# Bit_Reactor_modular.net
KiCad netlist of a schematic drawn in EAGLE
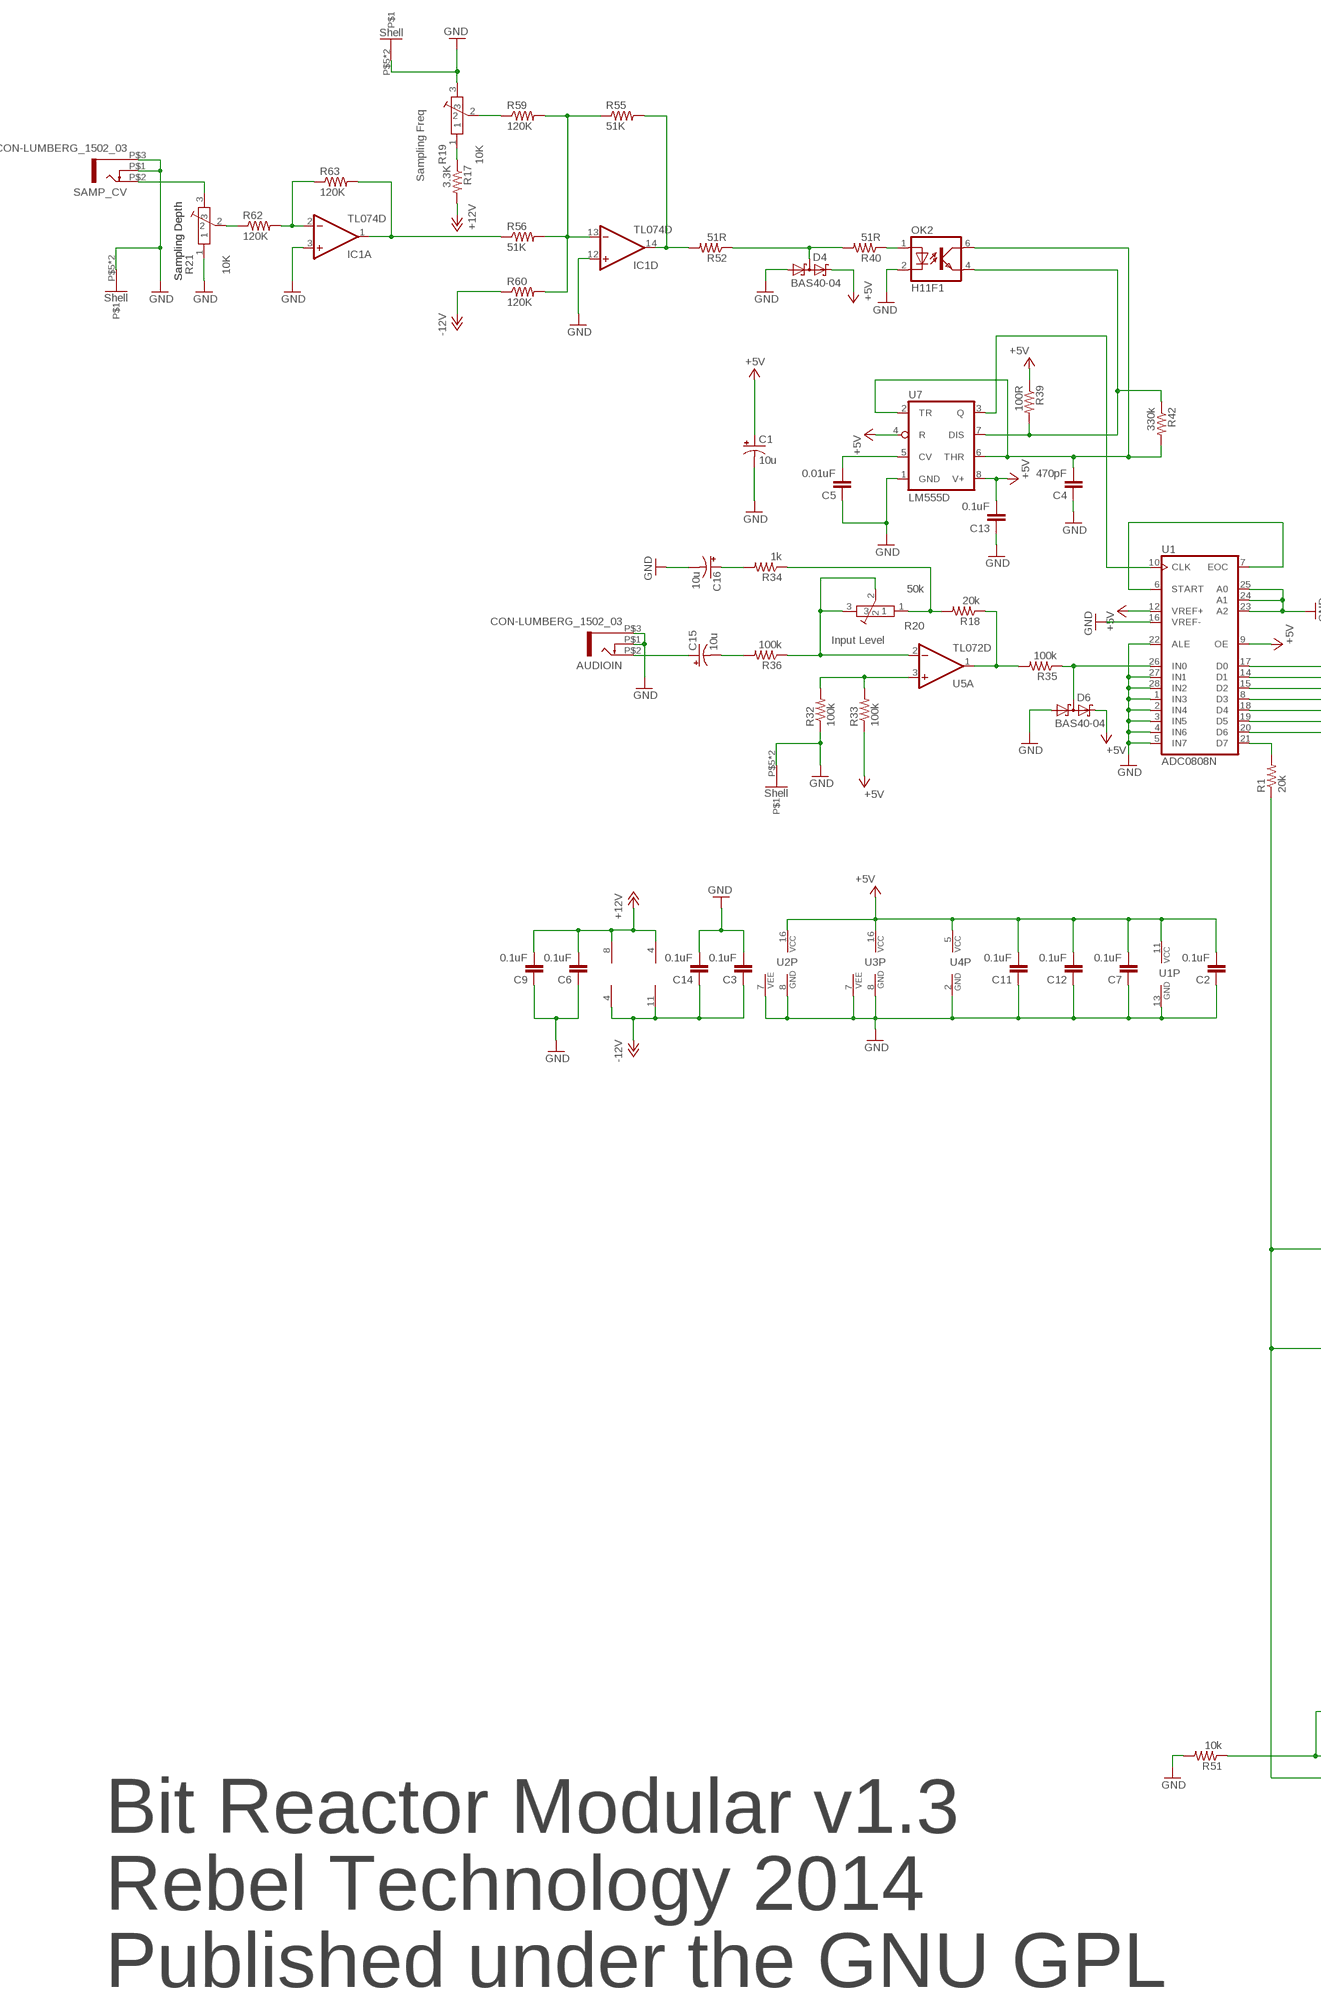
[diagram p0: schematic, sheet 1, part 1 of 2]
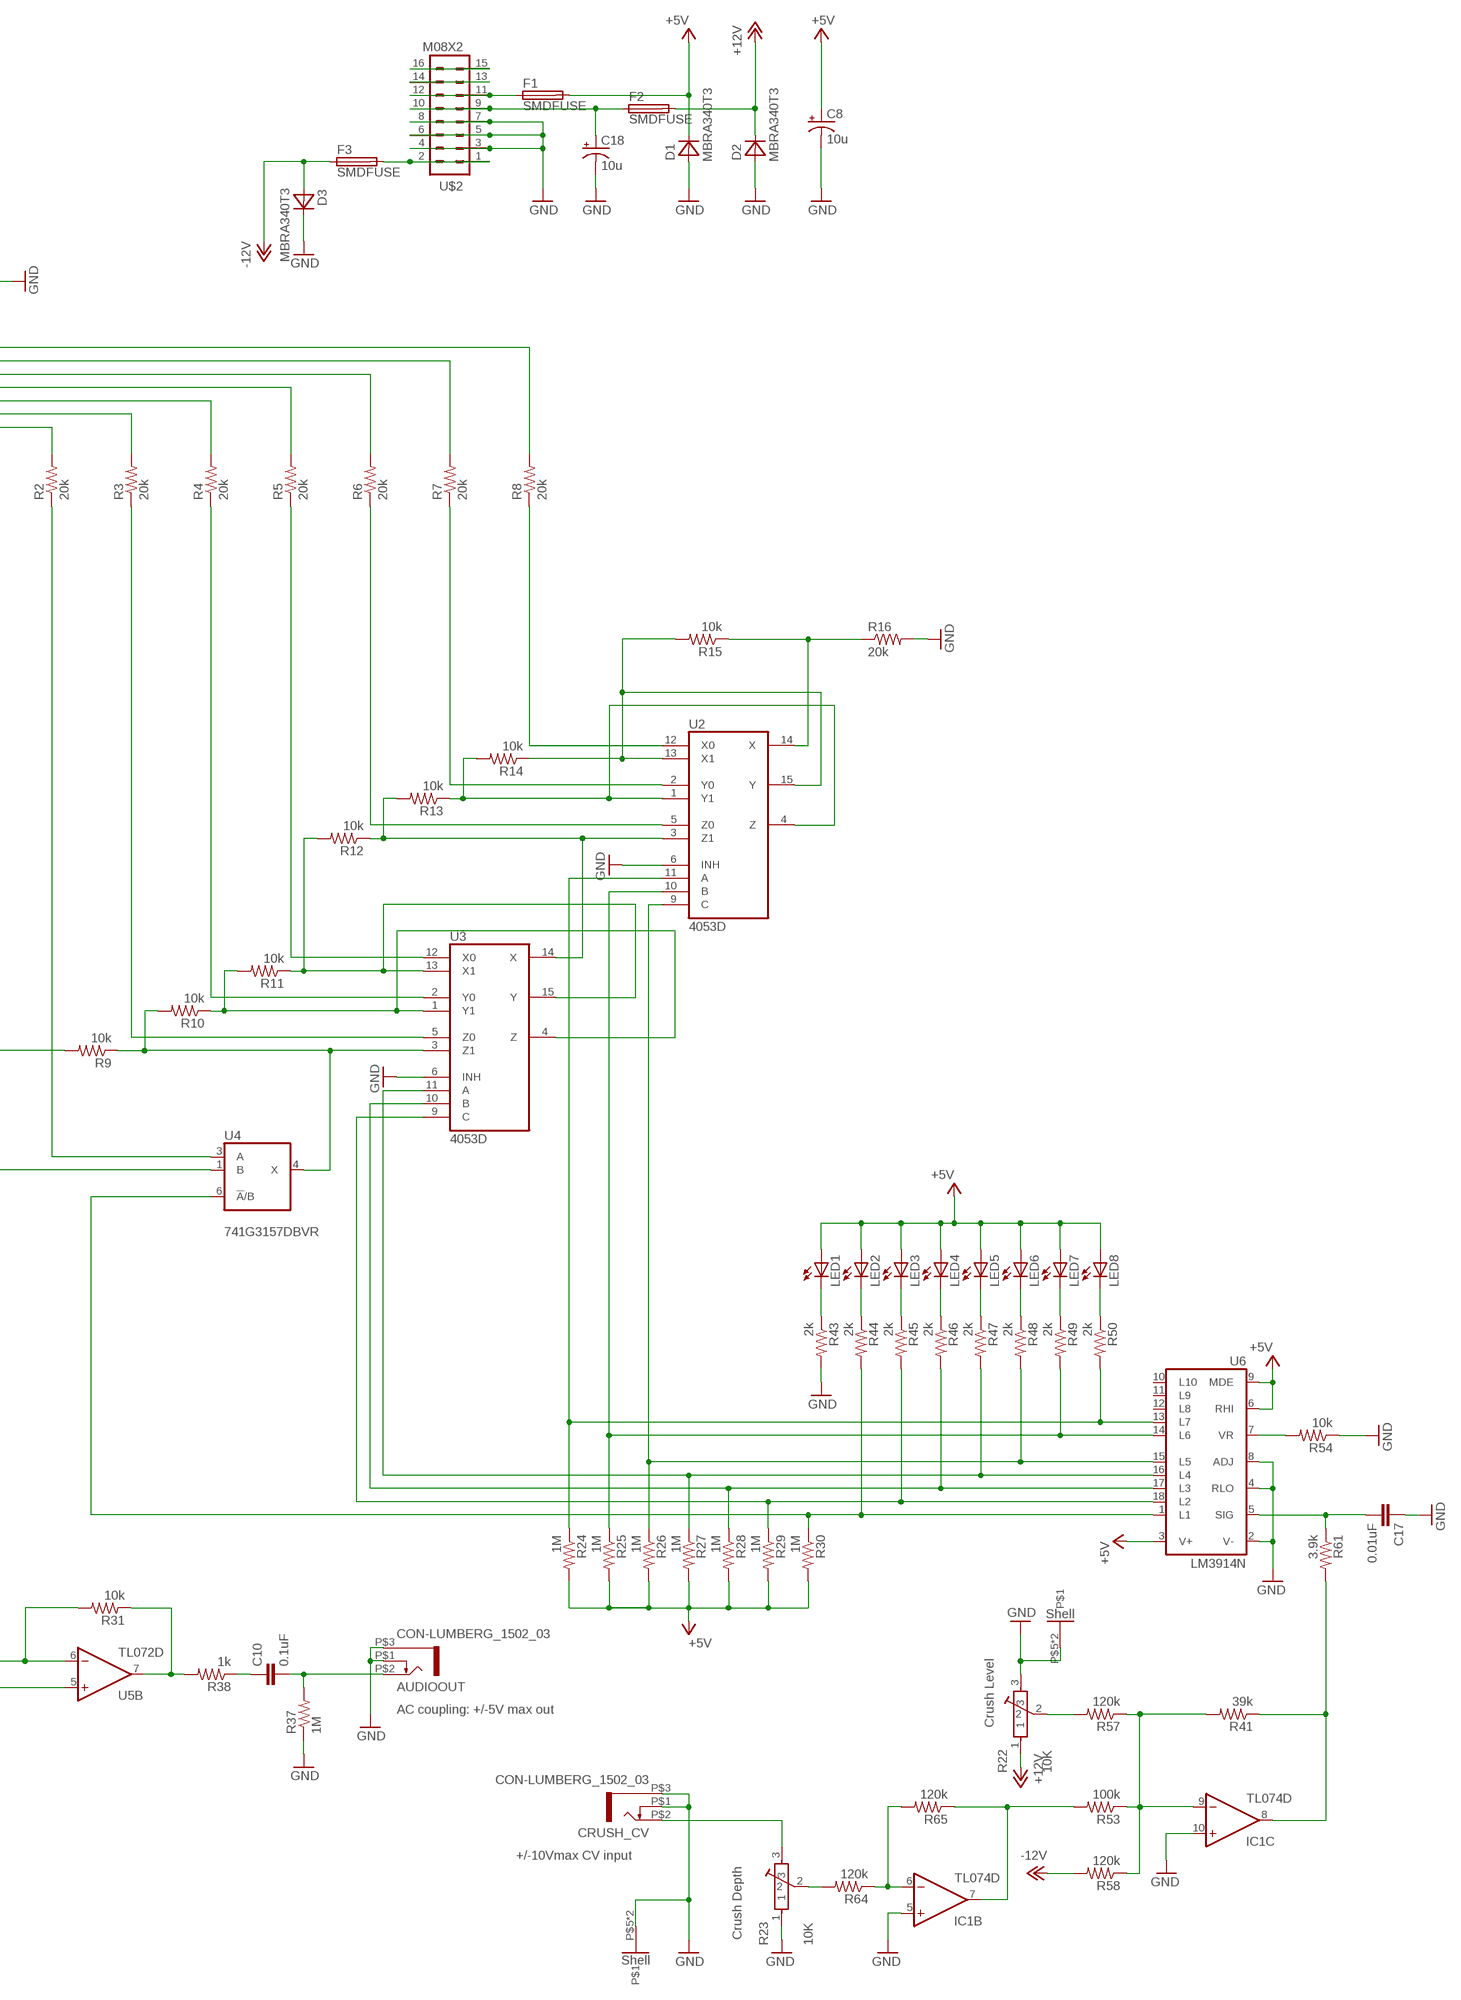
[diagram p1: schematic, sheet 1, part 2 of 2]

(export (version "E")
  (design (tool "Eeschema 10.0.6"))
  (components
    (comp (ref "AUDIOIN")
      (value "CON-LUMBERG_1502_03")
      (footprint "eagle-import:CON-LUMBERG_1502_03")
      (libsource (lib "eagle-import") (part "CON-LUMBERG_1502_03"))
    )
    (comp (ref "AUDIOOUT")
      (value "CON-LUMBERG_1502_03")
      (footprint "eagle-import:CON-LUMBERG_1502_03")
      (libsource (lib "eagle-import") (part "CON-LUMBERG_1502_03"))
    )
    (comp (ref "C1")
      (value "10u")
      (footprint "eagle-import:E2-5")
      (libsource (lib "eagle-import") (part "CPOL-USE2-5"))
    )
    (comp (ref "C2")
      (value "0.1uF")
      (footprint "eagle-import:C0402")
      (libsource (lib "eagle-import") (part "C-EUC0402"))
    )
    (comp (ref "C3")
      (value "0.1uF")
      (footprint "eagle-import:C0402")
      (libsource (lib "eagle-import") (part "C-EUC0402"))
    )
    (comp (ref "C4")
      (value "470pF")
      (footprint "eagle-import:C0402")
      (libsource (lib "eagle-import") (part "C-EUC0402"))
    )
    (comp (ref "C5")
      (value "0.01uF")
      (footprint "eagle-import:C0402")
      (libsource (lib "eagle-import") (part "C-EUC0402"))
    )
    (comp (ref "C6")
      (value "0.1uF")
      (footprint "eagle-import:C0402")
      (libsource (lib "eagle-import") (part "C-EUC0402"))
    )
    (comp (ref "C7")
      (value "0.1uF")
      (footprint "eagle-import:C0402")
      (libsource (lib "eagle-import") (part "C-EUC0402"))
    )
    (comp (ref "C8")
      (value "10u")
      (footprint "eagle-import:E2-5")
      (libsource (lib "eagle-import") (part "CPOL-USE2-5"))
    )
    (comp (ref "C9")
      (value "0.1uF")
      (footprint "eagle-import:C0402")
      (libsource (lib "eagle-import") (part "C-EUC0402"))
    )
    (comp (ref "C10")
      (value "0.1uF")
      (footprint "eagle-import:C0402")
      (libsource (lib "eagle-import") (part "C-EUC0402"))
    )
    (comp (ref "C11")
      (value "0.1uF")
      (footprint "eagle-import:C0402")
      (libsource (lib "eagle-import") (part "C-EUC0402"))
    )
    (comp (ref "C12")
      (value "0.1uF")
      (footprint "eagle-import:C0402")
      (libsource (lib "eagle-import") (part "C-EUC0402"))
    )
    (comp (ref "C13")
      (value "0.1uF")
      (footprint "eagle-import:C0402")
      (libsource (lib "eagle-import") (part "C-EUC0402"))
    )
    (comp (ref "C14")
      (value "0.1uF")
      (footprint "eagle-import:C0402")
      (libsource (lib "eagle-import") (part "C-EUC0402"))
    )
    (comp (ref "C15")
      (value "10u")
      (footprint "eagle-import:E2-5")
      (libsource (lib "eagle-import") (part "CPOL-USE2-5"))
    )
    (comp (ref "C16")
      (value "10u")
      (footprint "eagle-import:E2-5")
      (libsource (lib "eagle-import") (part "CPOL-USE2-5"))
    )
    (comp (ref "C17")
      (value "0.01uF")
      (footprint "eagle-import:C0402")
      (libsource (lib "eagle-import") (part "C-EUC0402"))
    )
    (comp (ref "C18")
      (value "10u")
      (footprint "eagle-import:E2-5")
      (libsource (lib "eagle-import") (part "CPOL-USE2-5"))
    )
    (comp (ref "CRUSH_CV")
      (value "CON-LUMBERG_1502_03")
      (footprint "eagle-import:CON-LUMBERG_1502_03")
      (libsource (lib "eagle-import") (part "CON-LUMBERG_1502_03"))
    )
    (comp (ref "D1")
      (value "MBRA340T3")
      (footprint "eagle-import:SMA")
      (libsource (lib "eagle-import") (part "MBRA340T3"))
    )
    (comp (ref "D2")
      (value "MBRA340T3")
      (footprint "eagle-import:SMA")
      (libsource (lib "eagle-import") (part "MBRA340T3"))
    )
    (comp (ref "D3")
      (value "MBRA340T3")
      (footprint "eagle-import:SMA")
      (libsource (lib "eagle-import") (part "MBRA340T3"))
    )
    (comp (ref "D4")
      (value "BAS40-04")
      (footprint "eagle-import:SOT23")
      (libsource (lib "eagle-import") (part "BAS40-04"))
    )
    (comp (ref "D6")
      (value "BAS40-04")
      (footprint "eagle-import:SOT23")
      (libsource (lib "eagle-import") (part "BAS40-04"))
    )
    (comp (ref "F1")
      (value "SMDFUSE")
      (footprint "eagle-import:1206")
      (libsource (lib "eagle-import") (part "SMDFUSE"))
    )
    (comp (ref "F2")
      (value "SMDFUSE")
      (footprint "eagle-import:1206")
      (libsource (lib "eagle-import") (part "SMDFUSE"))
    )
    (comp (ref "F3")
      (value "SMDFUSE")
      (footprint "eagle-import:1206")
      (libsource (lib "eagle-import") (part "SMDFUSE"))
    )
    (comp (ref "IC1")
      (value "TL074D")
      (footprint "eagle-import:SO14")
      (libsource (lib "eagle-import") (part "TL074D"))
    )
    (comp (ref "LED1")
      (value "LED3MM")
      (footprint "eagle-import:LED3MM")
      (libsource (lib "eagle-import") (part "LED3MM"))
    )
    (comp (ref "LED2")
      (value "LED3MM")
      (footprint "eagle-import:LED3MM")
      (libsource (lib "eagle-import") (part "LED3MM"))
    )
    (comp (ref "LED3")
      (value "LED3MM")
      (footprint "eagle-import:LED3MM")
      (libsource (lib "eagle-import") (part "LED3MM"))
    )
    (comp (ref "LED4")
      (value "LED3MM")
      (footprint "eagle-import:LED3MM")
      (libsource (lib "eagle-import") (part "LED3MM"))
    )
    (comp (ref "LED5")
      (value "LED3MM")
      (footprint "eagle-import:LED3MM")
      (libsource (lib "eagle-import") (part "LED3MM"))
    )
    (comp (ref "LED6")
      (value "LED3MM")
      (footprint "eagle-import:LED3MM")
      (libsource (lib "eagle-import") (part "LED3MM"))
    )
    (comp (ref "LED7")
      (value "LED3MM")
      (footprint "eagle-import:LED3MM")
      (libsource (lib "eagle-import") (part "LED3MM"))
    )
    (comp (ref "LED8")
      (value "LED3MM")
      (footprint "eagle-import:LED3MM")
      (libsource (lib "eagle-import") (part "LED3MM"))
    )
    (comp (ref "OK2")
      (value "H11F1")
      (footprint "eagle-import:DIL05")
      (fields (field (name "OC_FARNELL") "unknown") (field (name "OC_NEWARK") "unknown"))
      (libsource (lib "eagle-import") (part "H11F1"))
    )
    (comp (ref "R1")
      (value "20k")
      (footprint "eagle-import:R0805")
      (libsource (lib "eagle-import") (part "R-US_R0805"))
    )
    (comp (ref "R2")
      (value "20k")
      (footprint "eagle-import:R0805")
      (libsource (lib "eagle-import") (part "R-US_R0805"))
    )
    (comp (ref "R3")
      (value "20k")
      (footprint "eagle-import:R0805")
      (libsource (lib "eagle-import") (part "R-US_R0805"))
    )
    (comp (ref "R4")
      (value "20k")
      (footprint "eagle-import:R0805")
      (libsource (lib "eagle-import") (part "R-US_R0805"))
    )
    (comp (ref "R5")
      (value "20k")
      (footprint "eagle-import:R0805")
      (libsource (lib "eagle-import") (part "R-US_R0805"))
    )
    (comp (ref "R6")
      (value "20k")
      (footprint "eagle-import:R0805")
      (libsource (lib "eagle-import") (part "R-US_R0805"))
    )
    (comp (ref "R7")
      (value "20k")
      (footprint "eagle-import:R0805")
      (libsource (lib "eagle-import") (part "R-US_R0805"))
    )
    (comp (ref "R8")
      (value "20k")
      (footprint "eagle-import:R0805")
      (libsource (lib "eagle-import") (part "R-US_R0805"))
    )
    (comp (ref "R9")
      (value "10k")
      (footprint "eagle-import:R0805")
      (libsource (lib "eagle-import") (part "R-US_R0805"))
    )
    (comp (ref "R10")
      (value "10k")
      (footprint "eagle-import:R0805")
      (libsource (lib "eagle-import") (part "R-US_R0805"))
    )
    (comp (ref "R11")
      (value "10k")
      (footprint "eagle-import:R0805")
      (libsource (lib "eagle-import") (part "R-US_R0805"))
    )
    (comp (ref "R12")
      (value "10k")
      (footprint "eagle-import:R0805")
      (libsource (lib "eagle-import") (part "R-US_R0805"))
    )
    (comp (ref "R13")
      (value "10k")
      (footprint "eagle-import:R0805")
      (libsource (lib "eagle-import") (part "R-US_R0805"))
    )
    (comp (ref "R14")
      (value "10k")
      (footprint "eagle-import:R0805")
      (libsource (lib "eagle-import") (part "R-US_R0805"))
    )
    (comp (ref "R15")
      (value "10k")
      (footprint "eagle-import:R0805")
      (libsource (lib "eagle-import") (part "R-US_R0805"))
    )
    (comp (ref "R16")
      (value "20k")
      (footprint "eagle-import:R0805")
      (libsource (lib "eagle-import") (part "R-US_R0805"))
    )
    (comp (ref "R17")
      (value "3.3K")
      (footprint "eagle-import:R0805")
      (libsource (lib "eagle-import") (part "R-US_R0805"))
    )
    (comp (ref "R18")
      (value "20k")
      (footprint "eagle-import:R0805")
      (libsource (lib "eagle-import") (part "R-US_R0805"))
    )
    (comp (ref "R19")
      (value "10K")
      (footprint "eagle-import:POT-ALPS-RK09L1140")
      (libsource (lib "eagle-import") (part "POT-ALPS-RK09L1140"))
    )
    (comp (ref "R20")
      (value "50k")
      (footprint "eagle-import:POT-ALPS-RK09L1140")
      (libsource (lib "eagle-import") (part "POT-ALPS-RK09L1140"))
    )
    (comp (ref "R21")
      (value "10K")
      (footprint "eagle-import:POT-ALPS-RK09L1140")
      (libsource (lib "eagle-import") (part "POT-ALPS-RK09L1140"))
    )
    (comp (ref "R22")
      (value "10K")
      (footprint "eagle-import:POT-ALPS-RK09L1140")
      (libsource (lib "eagle-import") (part "POT-ALPS-RK09L1140"))
    )
    (comp (ref "R23")
      (value "10K")
      (footprint "eagle-import:POT-ALPS-RK09L1140")
      (libsource (lib "eagle-import") (part "POT-ALPS-RK09L1140"))
    )
    (comp (ref "R24")
      (value "1M")
      (footprint "eagle-import:R0402")
      (libsource (lib "eagle-import") (part "R-US_R0402"))
    )
    (comp (ref "R25")
      (value "1M")
      (footprint "eagle-import:R0402")
      (libsource (lib "eagle-import") (part "R-US_R0402"))
    )
    (comp (ref "R26")
      (value "1M")
      (footprint "eagle-import:R0402")
      (libsource (lib "eagle-import") (part "R-US_R0402"))
    )
    (comp (ref "R27")
      (value "1M")
      (footprint "eagle-import:R0402")
      (libsource (lib "eagle-import") (part "R-US_R0402"))
    )
    (comp (ref "R28")
      (value "1M")
      (footprint "eagle-import:R0402")
      (libsource (lib "eagle-import") (part "R-US_R0402"))
    )
    (comp (ref "R29")
      (value "1M")
      (footprint "eagle-import:R0402")
      (libsource (lib "eagle-import") (part "R-US_R0402"))
    )
    (comp (ref "R30")
      (value "1M")
      (footprint "eagle-import:R0402")
      (libsource (lib "eagle-import") (part "R-US_R0402"))
    )
    (comp (ref "R31")
      (value "10k")
      (footprint "eagle-import:R0402")
      (libsource (lib "eagle-import") (part "R-US_R0402"))
    )
    (comp (ref "R32")
      (value "100k")
      (footprint "eagle-import:R0402")
      (libsource (lib "eagle-import") (part "R-US_R0402"))
    )
    (comp (ref "R33")
      (value "100k")
      (footprint "eagle-import:R0402")
      (libsource (lib "eagle-import") (part "R-US_R0402"))
    )
    (comp (ref "R34")
      (value "1k")
      (footprint "eagle-import:R0805")
      (libsource (lib "eagle-import") (part "R-US_R0805"))
    )
    (comp (ref "R35")
      (value "100k")
      (footprint "eagle-import:R0402")
      (libsource (lib "eagle-import") (part "R-US_R0402"))
    )
    (comp (ref "R36")
      (value "100k")
      (footprint "eagle-import:R0402")
      (libsource (lib "eagle-import") (part "R-US_R0402"))
    )
    (comp (ref "R37")
      (value "1M")
      (footprint "eagle-import:R0402")
      (libsource (lib "eagle-import") (part "R-US_R0402"))
    )
    (comp (ref "R38")
      (value "1k")
      (footprint "eagle-import:R0805")
      (libsource (lib "eagle-import") (part "R-US_R0805"))
    )
    (comp (ref "R39")
      (value "100R")
      (footprint "eagle-import:R1206")
      (libsource (lib "eagle-import") (part "R-US_R1206"))
    )
    (comp (ref "R40")
      (value "51R")
      (footprint "eagle-import:R1206")
      (libsource (lib "eagle-import") (part "R-US_R1206"))
    )
    (comp (ref "R41")
      (value "39k")
      (footprint "eagle-import:R0402")
      (libsource (lib "eagle-import") (part "R-US_R0402"))
    )
    (comp (ref "R42")
      (value "330k")
      (footprint "eagle-import:R0402")
      (libsource (lib "eagle-import") (part "R-US_R0402"))
    )
    (comp (ref "R43")
      (value "2k")
      (footprint "eagle-import:R0402")
      (libsource (lib "eagle-import") (part "R-US_R0402"))
    )
    (comp (ref "R44")
      (value "2k")
      (footprint "eagle-import:R0402")
      (libsource (lib "eagle-import") (part "R-US_R0402"))
    )
    (comp (ref "R45")
      (value "2k")
      (footprint "eagle-import:R0402")
      (libsource (lib "eagle-import") (part "R-US_R0402"))
    )
    (comp (ref "R46")
      (value "2k")
      (footprint "eagle-import:R0402")
      (libsource (lib "eagle-import") (part "R-US_R0402"))
    )
    (comp (ref "R47")
      (value "2k")
      (footprint "eagle-import:R0402")
      (libsource (lib "eagle-import") (part "R-US_R0402"))
    )
    (comp (ref "R48")
      (value "2k")
      (footprint "eagle-import:R0402")
      (libsource (lib "eagle-import") (part "R-US_R0402"))
    )
    (comp (ref "R49")
      (value "2k")
      (footprint "eagle-import:R0402")
      (libsource (lib "eagle-import") (part "R-US_R0402"))
    )
    (comp (ref "R50")
      (value "2k")
      (footprint "eagle-import:R0402")
      (libsource (lib "eagle-import") (part "R-US_R0402"))
    )
    (comp (ref "R51")
      (value "10k")
      (footprint "eagle-import:R0402")
      (libsource (lib "eagle-import") (part "R-US_R0402"))
    )
    (comp (ref "R52")
      (value "51R")
      (footprint "eagle-import:R1206")
      (libsource (lib "eagle-import") (part "R-US_R1206"))
    )
    (comp (ref "R53")
      (value "100k")
      (footprint "eagle-import:R0402")
      (libsource (lib "eagle-import") (part "R-US_R0402"))
    )
    (comp (ref "R54")
      (value "10k")
      (footprint "eagle-import:R0805")
      (libsource (lib "eagle-import") (part "R-US_R0805"))
    )
    (comp (ref "R55")
      (value "51K")
      (footprint "eagle-import:R0402")
      (libsource (lib "eagle-import") (part "R-US_R0402"))
    )
    (comp (ref "R56")
      (value "51K")
      (footprint "eagle-import:R0402")
      (libsource (lib "eagle-import") (part "R-US_R0402"))
    )
    (comp (ref "R57")
      (value "120k")
      (footprint "eagle-import:R0402")
      (libsource (lib "eagle-import") (part "R-US_R0402"))
    )
    (comp (ref "R58")
      (value "120k")
      (footprint "eagle-import:R0402")
      (libsource (lib "eagle-import") (part "R-US_R0402"))
    )
    (comp (ref "R59")
      (value "120K")
      (footprint "eagle-import:R0402")
      (libsource (lib "eagle-import") (part "R-US_R0402"))
    )
    (comp (ref "R60")
      (value "120K")
      (footprint "eagle-import:R0402")
      (libsource (lib "eagle-import") (part "R-US_R0402"))
    )
    (comp (ref "R61")
      (value "3.9k")
      (footprint "eagle-import:R0402")
      (libsource (lib "eagle-import") (part "R-US_R0402"))
    )
    (comp (ref "R62")
      (value "120K")
      (footprint "eagle-import:R0402")
      (libsource (lib "eagle-import") (part "R-US_R0402"))
    )
    (comp (ref "R63")
      (value "120K")
      (footprint "eagle-import:R0402")
      (libsource (lib "eagle-import") (part "R-US_R0402"))
    )
    (comp (ref "R64")
      (value "120k")
      (footprint "eagle-import:R0402")
      (libsource (lib "eagle-import") (part "R-US_R0402"))
    )
    (comp (ref "R65")
      (value "120k")
      (footprint "eagle-import:R0402")
      (libsource (lib "eagle-import") (part "R-US_R0402"))
    )
    (comp (ref "SAMP_CV")
      (value "CON-LUMBERG_1502_03")
      (footprint "eagle-import:CON-LUMBERG_1502_03")
      (libsource (lib "eagle-import") (part "CON-LUMBERG_1502_03"))
    )
    (comp (ref "U$2")
      (value "M08X2")
      (footprint "eagle-import:2X8")
      (libsource (lib "eagle-import") (part "M08X2"))
    )
    (comp (ref "U1")
      (value "ADC0808N")
      (footprint "eagle-import:DIL28-6")
      (libsource (lib "eagle-import") (part "ADC0808N"))
    )
    (comp (ref "U2")
      (value "4053D")
      (footprint "eagle-import:SO16")
      (libsource (lib "eagle-import") (part "4053D"))
    )
    (comp (ref "U3")
      (value "4053D")
      (footprint "eagle-import:SO16")
      (libsource (lib "eagle-import") (part "4053D"))
    )
    (comp (ref "U4")
      (value "741G3157DBVR")
      (footprint "eagle-import:DBV_R-PDSO-G6")
      (libsource (lib "eagle-import") (part "741G3157DBVR"))
    )
    (comp (ref "U5")
      (value "TL072D")
      (footprint "eagle-import:SO08")
      (libsource (lib "eagle-import") (part "TL072D"))
    )
    (comp (ref "U6")
      (value "LM3914N")
      (footprint "eagle-import:DIL18")
      (libsource (lib "eagle-import") (part "LM3914N"))
    )
    (comp (ref "U7")
      (value "LM555D")
      (footprint "eagle-import:SO08")
      (libsource (lib "eagle-import") (part "555DLM"))
    )
  )
  (nets
    (net (code "1") (name "+5V") (class "Default")
      (node (ref "C1") (pin "+") (pinfunction "+_+") (pintype "passive"))
      (node (ref "C11") (pin "2") (pinfunction "2_2") (pintype "passive"))
      (node (ref "C12") (pin "2") (pinfunction "2_2") (pintype "passive"))
      (node (ref "C13") (pin "2") (pinfunction "2_2") (pintype "passive"))
      (node (ref "C2") (pin "2") (pinfunction "2_2") (pintype "passive"))
      (node (ref "C7") (pin "2") (pinfunction "2_2") (pintype "passive"))
      (node (ref "C8") (pin "+") (pinfunction "+_+") (pintype "passive"))
      (node (ref "D1") (pin "C") (pinfunction "C_C") (pintype "passive"))
      (node (ref "D4") (pin "2") (pinfunction "C2_2") (pintype "passive"))
      (node (ref "D6") (pin "2") (pinfunction "C2_2") (pintype "passive"))
      (node (ref "F1") (pin "2") (pinfunction "2_2") (pintype "passive"))
      (node (ref "LED1") (pin "A") (pinfunction "A_A") (pintype "passive"))
      (node (ref "LED2") (pin "A") (pinfunction "A_A") (pintype "passive"))
      (node (ref "LED3") (pin "A") (pinfunction "A_A") (pintype "passive"))
      (node (ref "LED4") (pin "A") (pinfunction "A_A") (pintype "passive"))
      (node (ref "LED5") (pin "A") (pinfunction "A_A") (pintype "passive"))
      (node (ref "LED6") (pin "A") (pinfunction "A_A") (pintype "passive"))
      (node (ref "LED7") (pin "A") (pinfunction "A_A") (pintype "passive"))
      (node (ref "LED8") (pin "A") (pinfunction "A_A") (pintype "passive"))
      (node (ref "R24") (pin "2") (pinfunction "2_2") (pintype "passive"))
      (node (ref "R25") (pin "2") (pinfunction "2_2") (pintype "passive"))
      (node (ref "R26") (pin "2") (pinfunction "2_2") (pintype "passive"))
      (node (ref "R27") (pin "2") (pinfunction "2_2") (pintype "passive"))
      (node (ref "R28") (pin "2") (pinfunction "2_2") (pintype "passive"))
      (node (ref "R29") (pin "2") (pinfunction "2_2") (pintype "passive"))
      (node (ref "R30") (pin "2") (pinfunction "2_2") (pintype "passive"))
      (node (ref "R33") (pin "1") (pinfunction "1_1") (pintype "passive"))
      (node (ref "R39") (pin "1") (pinfunction "1_1") (pintype "passive"))
      (node (ref "U1") (pin "11") (pinfunction "VCC_11") (pintype "power_in"))
      (node (ref "U1") (pin "12") (pinfunction "VREF+_12") (pintype "input"))
      (node (ref "U1") (pin "9") (pinfunction "OE_9") (pintype "input"))
      (node (ref "U2") (pin "16") (pinfunction "VCC_16") (pintype "power_in"))
      (node (ref "U3") (pin "16") (pinfunction "VCC_16") (pintype "power_in"))
      (node (ref "U4") (pin "5") (pinfunction "VCC_5") (pintype "power_in"))
      (node (ref "U6") (pin "3") (pinfunction "V+_3") (pintype "power_in"))
      (node (ref "U6") (pin "6") (pinfunction "RHI_6") (pintype "input"))
      (node (ref "U6") (pin "9") (pinfunction "MDE_9") (pintype "input"))
      (node (ref "U7") (pin "4") (pinfunction "R_4") (pintype "input"))
      (node (ref "U7") (pin "8") (pinfunction "V+_8") (pintype "power_in"))
    )
    (net (code "2") (name "+12V") (class "Default")
      (node (ref "C6") (pin "2") (pinfunction "2_2") (pintype "passive"))
      (node (ref "C9") (pin "2") (pinfunction "2_2") (pintype "passive"))
      (node (ref "D2") (pin "C") (pinfunction "C_C") (pintype "passive"))
      (node (ref "F2") (pin "2") (pinfunction "2_2") (pintype "passive"))
      (node (ref "IC1") (pin "4") (pinfunction "V+_4") (pintype "power_in"))
      (node (ref "R17") (pin "2") (pinfunction "2_2") (pintype "passive"))
      (node (ref "R22") (pin "1") (pinfunction "1_1") (pintype "bidirectional"))
      (node (ref "U5") (pin "8") (pinfunction "V+_8") (pintype "power_in"))
    )
    (net (code "3") (name "-12V") (class "Default")
      (node (ref "C14") (pin "1") (pinfunction "1_1") (pintype "passive"))
      (node (ref "C3") (pin "1") (pinfunction "1_1") (pintype "passive"))
      (node (ref "D3") (pin "A") (pinfunction "A_A") (pintype "passive"))
      (node (ref "F3") (pin "1") (pinfunction "1_1") (pintype "passive"))
      (node (ref "IC1") (pin "11") (pinfunction "V-_11") (pintype "power_in"))
      (node (ref "R58") (pin "2") (pinfunction "2_2") (pintype "passive"))
      (node (ref "R60") (pin "1") (pinfunction "1_1") (pintype "passive"))
      (node (ref "U5") (pin "4") (pinfunction "V-_4") (pintype "power_in"))
    )
    (net (code "4") (name "GND") (class "Default")
      (node (ref "AUDIOIN") (pin "P$1") (pinfunction "4_P$1") (pintype "passive"))
      (node (ref "AUDIOIN") (pin "P$3") (pinfunction "5_P$3") (pintype "passive"))
      (node (ref "AUDIOOUT") (pin "P$1") (pinfunction "4_P$1") (pintype "passive"))
      (node (ref "AUDIOOUT") (pin "P$3") (pinfunction "5_P$3") (pintype "passive"))
      (node (ref "C1") (pin "-") (pinfunction "-_-") (pintype "passive"))
      (node (ref "C11") (pin "1") (pinfunction "1_1") (pintype "passive"))
      (node (ref "C12") (pin "1") (pinfunction "1_1") (pintype "passive"))
      (node (ref "C13") (pin "1") (pinfunction "1_1") (pintype "passive"))
      (node (ref "C14") (pin "2") (pinfunction "2_2") (pintype "passive"))
      (node (ref "C16") (pin "-") (pinfunction "-_-") (pintype "passive"))
      (node (ref "C17") (pin "1") (pinfunction "1_1") (pintype "passive"))
      (node (ref "C18") (pin "-") (pinfunction "-_-") (pintype "passive"))
      (node (ref "C2") (pin "1") (pinfunction "1_1") (pintype "passive"))
      (node (ref "C3") (pin "2") (pinfunction "2_2") (pintype "passive"))
      (node (ref "C4") (pin "1") (pinfunction "1_1") (pintype "passive"))
      (node (ref "C5") (pin "1") (pinfunction "1_1") (pintype "passive"))
      (node (ref "C6") (pin "1") (pinfunction "1_1") (pintype "passive"))
      (node (ref "C7") (pin "1") (pinfunction "1_1") (pintype "passive"))
      (node (ref "C8") (pin "-") (pinfunction "-_-") (pintype "passive"))
      (node (ref "C9") (pin "1") (pinfunction "1_1") (pintype "passive"))
      (node (ref "CRUSH_CV") (pin "P$1") (pinfunction "4_P$1") (pintype "passive"))
      (node (ref "CRUSH_CV") (pin "P$3") (pinfunction "5_P$3") (pintype "passive"))
      (node (ref "D1") (pin "A") (pinfunction "A_A") (pintype "passive"))
      (node (ref "D2") (pin "A") (pinfunction "A_A") (pintype "passive"))
      (node (ref "D3") (pin "C") (pinfunction "C_C") (pintype "passive"))
      (node (ref "D4") (pin "1") (pinfunction "A1_1") (pintype "passive"))
      (node (ref "D6") (pin "1") (pinfunction "A1_1") (pintype "passive"))
      (node (ref "IC1") (pin "10") (pinfunction "+IN_10") (pintype "input"))
      (node (ref "IC1") (pin "12") (pinfunction "+IN_12") (pintype "input"))
      (node (ref "IC1") (pin "3") (pinfunction "+IN_3") (pintype "input"))
      (node (ref "IC1") (pin "5") (pinfunction "+IN_5") (pintype "input"))
      (node (ref "OK2") (pin "2") (pinfunction "C_2") (pintype "passive"))
      (node (ref "R16") (pin "2") (pinfunction "2_2") (pintype "passive"))
      (node (ref "R19") (pin "3") (pinfunction "3_3") (pintype "bidirectional"))
      (node (ref "R19") (pin "P$5") (pinfunction "P$1_P$5") (pintype "bidirectional"))
      (node (ref "R19") (pin "P$6") (pinfunction "P$1_P$6") (pintype "bidirectional"))
      (node (ref "R20") (pin "P$5") (pinfunction "P$1_P$5") (pintype "bidirectional"))
      (node (ref "R20") (pin "P$6") (pinfunction "P$1_P$6") (pintype "bidirectional"))
      (node (ref "R21") (pin "1") (pinfunction "1_1") (pintype "bidirectional"))
      (node (ref "R21") (pin "P$5") (pinfunction "P$1_P$5") (pintype "bidirectional"))
      (node (ref "R21") (pin "P$6") (pinfunction "P$1_P$6") (pintype "bidirectional"))
      (node (ref "R22") (pin "3") (pinfunction "3_3") (pintype "bidirectional"))
      (node (ref "R22") (pin "P$5") (pinfunction "P$1_P$5") (pintype "bidirectional"))
      (node (ref "R22") (pin "P$6") (pinfunction "P$1_P$6") (pintype "bidirectional"))
      (node (ref "R23") (pin "1") (pinfunction "1_1") (pintype "bidirectional"))
      (node (ref "R23") (pin "P$5") (pinfunction "P$1_P$5") (pintype "bidirectional"))
      (node (ref "R23") (pin "P$6") (pinfunction "P$1_P$6") (pintype "bidirectional"))
      (node (ref "R32") (pin "1") (pinfunction "1_1") (pintype "passive"))
      (node (ref "R37") (pin "1") (pinfunction "1_1") (pintype "passive"))
      (node (ref "R43") (pin "2") (pinfunction "2_2") (pintype "passive"))
      (node (ref "R51") (pin "2") (pinfunction "2_2") (pintype "passive"))
      (node (ref "R54") (pin "1") (pinfunction "1_1") (pintype "passive"))
      (node (ref "SAMP_CV") (pin "P$1") (pinfunction "4_P$1") (pintype "passive"))
      (node (ref "SAMP_CV") (pin "P$3") (pinfunction "5_P$3") (pintype "passive"))
      (node (ref "U$2") (pin "3") (pinfunction "3_3") (pintype "passive"))
      (node (ref "U$2") (pin "4") (pinfunction "4_4") (pintype "passive"))
      (node (ref "U$2") (pin "5") (pinfunction "5_5") (pintype "passive"))
      (node (ref "U$2") (pin "6") (pinfunction "6_6") (pintype "passive"))
      (node (ref "U$2") (pin "7") (pinfunction "7_7") (pintype "passive"))
      (node (ref "U$2") (pin "8") (pinfunction "8_8") (pintype "passive"))
      (node (ref "U1") (pin "1") (pinfunction "IN3_1") (pintype "input"))
      (node (ref "U1") (pin "13") (pinfunction "GND_13") (pintype "power_in"))
      (node (ref "U1") (pin "16") (pinfunction "VREF-_16") (pintype "input"))
      (node (ref "U1") (pin "2") (pinfunction "IN4_2") (pintype "input"))
      (node (ref "U1") (pin "22") (pinfunction "ALE_22") (pintype "input"))
      (node (ref "U1") (pin "23") (pinfunction "A2_23") (pintype "input"))
      (node (ref "U1") (pin "24") (pinfunction "A1_24") (pintype "input"))
      (node (ref "U1") (pin "25") (pinfunction "A0_25") (pintype "input"))
      (node (ref "U1") (pin "27") (pinfunction "IN1_27") (pintype "input"))
      (node (ref "U1") (pin "28") (pinfunction "IN2_28") (pintype "input"))
      (node (ref "U1") (pin "3") (pinfunction "IN5_3") (pintype "input"))
      (node (ref "U1") (pin "4") (pinfunction "IN6_4") (pintype "input"))
      (node (ref "U1") (pin "5") (pinfunction "IN7_5") (pintype "input"))
      (node (ref "U2") (pin "6") (pinfunction "INH_6") (pintype "input"))
      (node (ref "U2") (pin "7") (pinfunction "VEE_7") (pintype "power_in"))
      (node (ref "U2") (pin "8") (pinfunction "GND_8") (pintype "power_in"))
      (node (ref "U3") (pin "6") (pinfunction "INH_6") (pintype "input"))
      (node (ref "U3") (pin "7") (pinfunction "VEE_7") (pintype "power_in"))
      (node (ref "U3") (pin "8") (pinfunction "GND_8") (pintype "power_in"))
      (node (ref "U4") (pin "2") (pinfunction "GND_2") (pintype "power_in"))
      (node (ref "U6") (pin "2") (pinfunction "V-_2") (pintype "power_in"))
      (node (ref "U6") (pin "4") (pinfunction "RLO_4") (pintype "input"))
      (node (ref "U6") (pin "8") (pinfunction "ADJ_8") (pintype "input"))
      (node (ref "U7") (pin "1") (pinfunction "GND_1") (pintype "power_in"))
    )
    (net (code "5") (name "Net-(AUDIOIN-3)") (class "Default")
      (node (ref "AUDIOIN") (pin "P$2") (pinfunction "3_P$2") (pintype "passive"))
      (node (ref "C15") (pin "+") (pinfunction "+_+") (pintype "passive"))
    )
    (net (code "6") (name "Net-(AUDIOOUT-3)") (class "Default")
      (node (ref "AUDIOOUT") (pin "P$2") (pinfunction "3_P$2") (pintype "passive"))
      (node (ref "C10") (pin "2") (pinfunction "2_2") (pintype "passive"))
      (node (ref "R37") (pin "2") (pinfunction "2_2") (pintype "passive"))
    )
    (net (code "7") (name "Net-(C10-Pad1)") (class "Default")
      (node (ref "C10") (pin "1") (pinfunction "1_1") (pintype "passive"))
      (node (ref "R38") (pin "1") (pinfunction "1_1") (pintype "passive"))
    )
    (net (code "8") (name "Net-(C15-Pad-)") (class "Default")
      (node (ref "C15") (pin "-") (pinfunction "-_-") (pintype "passive"))
      (node (ref "R36") (pin "2") (pinfunction "2_2") (pintype "passive"))
    )
    (net (code "9") (name "Net-(C16-Pad+)") (class "Default")
      (node (ref "C16") (pin "+") (pinfunction "+_+") (pintype "passive"))
      (node (ref "R34") (pin "2") (pinfunction "2_2") (pintype "passive"))
    )
    (net (code "10") (name "Net-(C18-Pad+)") (class "Default")
      (node (ref "C18") (pin "+") (pinfunction "+_+") (pintype "passive"))
      (node (ref "F2") (pin "1") (pinfunction "1_1") (pintype "passive"))
      (node (ref "U$2") (pin "10") (pinfunction "10_10") (pintype "passive"))
      (node (ref "U$2") (pin "9") (pinfunction "9_9") (pintype "passive"))
    )
    (net (code "11") (name "Net-(CRUSH_CV-3)") (class "Default")
      (node (ref "CRUSH_CV") (pin "P$2") (pinfunction "3_P$2") (pintype "passive"))
      (node (ref "R23") (pin "3") (pinfunction "3_3") (pintype "bidirectional"))
    )
    (net (code "12") (name "Net-(D4-C1A2)") (class "Default")
      (node (ref "D4") (pin "3") (pinfunction "C1A2_3") (pintype "passive"))
      (node (ref "R40") (pin "2") (pinfunction "2_2") (pintype "passive"))
      (node (ref "R52") (pin "1") (pinfunction "1_1") (pintype "passive"))
    )
    (net (code "13") (name "Net-(D6-C1A2)") (class "Default")
      (node (ref "D6") (pin "3") (pinfunction "C1A2_3") (pintype "passive"))
      (node (ref "R35") (pin "1") (pinfunction "1_1") (pintype "passive"))
      (node (ref "U1") (pin "26") (pinfunction "IN0_26") (pintype "input"))
    )
    (net (code "14") (name "Net-(F1-Pad1)") (class "Default")
      (node (ref "F1") (pin "1") (pinfunction "1_1") (pintype "passive"))
      (node (ref "U$2") (pin "11") (pinfunction "11_11") (pintype "passive"))
      (node (ref "U$2") (pin "12") (pinfunction "12_12") (pintype "passive"))
    )
    (net (code "15") (name "Net-(F3-Pad2)") (class "Default")
      (node (ref "F3") (pin "2") (pinfunction "2_2") (pintype "passive"))
      (node (ref "U$2") (pin "1") (pinfunction "1_1") (pintype "passive"))
      (node (ref "U$2") (pin "2") (pinfunction "2_2") (pintype "passive"))
    )
    (net (code "16") (name "Net-(IC1A--IN)") (class "Default")
      (node (ref "IC1") (pin "2") (pinfunction "-IN_2") (pintype "input"))
      (node (ref "R62") (pin "2") (pinfunction "2_2") (pintype "passive"))
      (node (ref "R63") (pin "1") (pinfunction "1_1") (pintype "passive"))
    )
    (net (code "17") (name "Net-(IC1A-OUT)") (class "Default")
      (node (ref "IC1") (pin "1") (pinfunction "OUT_1") (pintype "output"))
      (node (ref "R56") (pin "1") (pinfunction "1_1") (pintype "passive"))
      (node (ref "R63") (pin "2") (pinfunction "2_2") (pintype "passive"))
    )
    (net (code "18") (name "Net-(IC1B--IN)") (class "Default")
      (node (ref "IC1") (pin "6") (pinfunction "-IN_6") (pintype "input"))
      (node (ref "R64") (pin "1") (pinfunction "1_1") (pintype "passive"))
      (node (ref "R65") (pin "2") (pinfunction "2_2") (pintype "passive"))
    )
    (net (code "19") (name "Net-(IC1B-OUT)") (class "Default")
      (node (ref "IC1") (pin "7") (pinfunction "OUT_7") (pintype "output"))
      (node (ref "R53") (pin "2") (pinfunction "2_2") (pintype "passive"))
      (node (ref "R65") (pin "1") (pinfunction "1_1") (pintype "passive"))
    )
    (net (code "20") (name "Net-(IC1C--IN)") (class "Default")
      (node (ref "IC1") (pin "9") (pinfunction "-IN_9") (pintype "input"))
      (node (ref "R41") (pin "2") (pinfunction "2_2") (pintype "passive"))
      (node (ref "R53") (pin "1") (pinfunction "1_1") (pintype "passive"))
      (node (ref "R57") (pin "1") (pinfunction "1_1") (pintype "passive"))
      (node (ref "R58") (pin "1") (pinfunction "1_1") (pintype "passive"))
    )
    (net (code "21") (name "Net-(IC1C-OUT)") (class "Default")
      (node (ref "IC1") (pin "8") (pinfunction "OUT_8") (pintype "output"))
      (node (ref "R41") (pin "1") (pinfunction "1_1") (pintype "passive"))
      (node (ref "R61") (pin "2") (pinfunction "2_2") (pintype "passive"))
    )
    (net (code "22") (name "Net-(IC1D--IN)") (class "Default")
      (node (ref "IC1") (pin "13") (pinfunction "-IN_13") (pintype "input"))
      (node (ref "R55") (pin "1") (pinfunction "1_1") (pintype "passive"))
      (node (ref "R56") (pin "2") (pinfunction "2_2") (pintype "passive"))
      (node (ref "R59") (pin "2") (pinfunction "2_2") (pintype "passive"))
      (node (ref "R60") (pin "2") (pinfunction "2_2") (pintype "passive"))
    )
    (net (code "23") (name "Net-(IC1D-OUT)") (class "Default")
      (node (ref "IC1") (pin "14") (pinfunction "OUT_14") (pintype "output"))
      (node (ref "R52") (pin "2") (pinfunction "2_2") (pintype "passive"))
      (node (ref "R55") (pin "2") (pinfunction "2_2") (pintype "passive"))
    )
    (net (code "24") (name "Net-(LED1-C)") (class "Default")
      (node (ref "LED1") (pin "K") (pinfunction "C_K") (pintype "passive"))
      (node (ref "R43") (pin "1") (pinfunction "1_1") (pintype "passive"))
    )
    (net (code "25") (name "Net-(LED2-C)") (class "Default")
      (node (ref "LED2") (pin "K") (pinfunction "C_K") (pintype "passive"))
      (node (ref "R44") (pin "1") (pinfunction "1_1") (pintype "passive"))
    )
    (net (code "26") (name "Net-(LED3-C)") (class "Default")
      (node (ref "LED3") (pin "K") (pinfunction "C_K") (pintype "passive"))
      (node (ref "R45") (pin "1") (pinfunction "1_1") (pintype "passive"))
    )
    (net (code "27") (name "Net-(LED4-C)") (class "Default")
      (node (ref "LED4") (pin "K") (pinfunction "C_K") (pintype "passive"))
      (node (ref "R46") (pin "1") (pinfunction "1_1") (pintype "passive"))
    )
    (net (code "28") (name "Net-(LED5-C)") (class "Default")
      (node (ref "LED5") (pin "K") (pinfunction "C_K") (pintype "passive"))
      (node (ref "R47") (pin "1") (pinfunction "1_1") (pintype "passive"))
    )
    (net (code "29") (name "Net-(LED6-C)") (class "Default")
      (node (ref "LED6") (pin "K") (pinfunction "C_K") (pintype "passive"))
      (node (ref "R48") (pin "1") (pinfunction "1_1") (pintype "passive"))
    )
    (net (code "30") (name "Net-(LED7-C)") (class "Default")
      (node (ref "LED7") (pin "K") (pinfunction "C_K") (pintype "passive"))
      (node (ref "R49") (pin "1") (pinfunction "1_1") (pintype "passive"))
    )
    (net (code "31") (name "Net-(LED8-C)") (class "Default")
      (node (ref "LED8") (pin "K") (pinfunction "C_K") (pintype "passive"))
      (node (ref "R50") (pin "1") (pinfunction "1_1") (pintype "passive"))
    )
    (net (code "32") (name "Net-(OK2-A)") (class "Default")
      (node (ref "OK2") (pin "1") (pinfunction "A_1") (pintype "passive"))
      (node (ref "R40") (pin "1") (pinfunction "1_1") (pintype "passive"))
    )
    (net (code "33") (name "Net-(OK2-COL)") (class "Default")
      (node (ref "C4") (pin "2") (pinfunction "2_2") (pintype "passive"))
      (node (ref "OK2") (pin "6") (pinfunction "COL_6") (pintype "passive"))
      (node (ref "R42") (pin "2") (pinfunction "2_2") (pintype "passive"))
      (node (ref "U7") (pin "2") (pinfunction "TR_2") (pintype "input"))
      (node (ref "U7") (pin "6") (pinfunction "THR_6") (pintype "input"))
    )
    (net (code "34") (name "Net-(OK2-EMIT)") (class "Default")
      (node (ref "OK2") (pin "4") (pinfunction "EMIT_4") (pintype "passive"))
      (node (ref "R39") (pin "2") (pinfunction "2_2") (pintype "passive"))
      (node (ref "R42") (pin "1") (pinfunction "1_1") (pintype "passive"))
      (node (ref "U7") (pin "7") (pinfunction "DIS_7") (pintype "input"))
    )
    (net (code "35") (name "Net-(R17-Pad1)") (class "Default")
      (node (ref "R17") (pin "1") (pinfunction "1_1") (pintype "passive"))
      (node (ref "R19") (pin "1") (pinfunction "1_1") (pintype "bidirectional"))
    )
    (net (code "36") (name "Net-(R18-Pad2)") (class "Default")
      (node (ref "R18") (pin "2") (pinfunction "2_2") (pintype "passive"))
      (node (ref "R20") (pin "1") (pinfunction "1_1") (pintype "bidirectional"))
      (node (ref "R34") (pin "1") (pinfunction "1_1") (pintype "passive"))
    )
    (net (code "37") (name "Net-(R19-Pad2)") (class "Default")
      (node (ref "R19") (pin "2") (pinfunction "2_2") (pintype "bidirectional"))
      (node (ref "R59") (pin "1") (pinfunction "1_1") (pintype "passive"))
    )
    (net (code "38") (name "Net-(R21-Pad2)") (class "Default")
      (node (ref "R21") (pin "2") (pinfunction "2_2") (pintype "bidirectional"))
      (node (ref "R62") (pin "1") (pinfunction "1_1") (pintype "passive"))
    )
    (net (code "39") (name "Net-(R22-Pad2)") (class "Default")
      (node (ref "R22") (pin "2") (pinfunction "2_2") (pintype "bidirectional"))
      (node (ref "R57") (pin "2") (pinfunction "2_2") (pintype "passive"))
    )
    (net (code "40") (name "Net-(R23-Pad2)") (class "Default")
      (node (ref "R23") (pin "2") (pinfunction "2_2") (pintype "bidirectional"))
      (node (ref "R64") (pin "2") (pinfunction "2_2") (pintype "passive"))
    )
    (net (code "41") (name "Net-(SAMP_CV-3)") (class "Default")
      (node (ref "R21") (pin "3") (pinfunction "3_3") (pintype "bidirectional"))
      (node (ref "SAMP_CV") (pin "P$2") (pinfunction "3_P$2") (pintype "passive"))
    )
    (net (code "42") (name "Net-(U$2-Pad13)") (class "Default")
      (node (ref "U$2") (pin "13") (pinfunction "13_13") (pintype "passive"))
      (node (ref "U$2") (pin "14") (pinfunction "14_14") (pintype "passive"))
    )
    (net (code "43") (name "Net-(U$2-Pad15)") (class "Default")
      (node (ref "U$2") (pin "15") (pinfunction "15_15") (pintype "passive"))
      (node (ref "U$2") (pin "16") (pinfunction "16_16") (pintype "passive"))
    )
    (net (code "44") (name "Net-(U1A-CLK)") (class "Default")
      (node (ref "U1") (pin "10") (pinfunction "CLK_10") (pintype "input"))
      (node (ref "U7") (pin "3") (pinfunction "Q_3") (pintype "output"))
    )
    (net (code "45") (name "Net-(U1A-D0)") (class "Default")
      (node (ref "R8") (pin "2") (pinfunction "2_2") (pintype "passive"))
      (node (ref "U1") (pin "17") (pinfunction "D0_17") (pintype "tri_state"))
    )
    (net (code "46") (name "Net-(U1A-D1)") (class "Default")
      (node (ref "R7") (pin "2") (pinfunction "2_2") (pintype "passive"))
      (node (ref "U1") (pin "14") (pinfunction "D1_14") (pintype "tri_state"))
    )
    (net (code "47") (name "Net-(U1A-D2)") (class "Default")
      (node (ref "R6") (pin "2") (pinfunction "2_2") (pintype "passive"))
      (node (ref "U1") (pin "15") (pinfunction "D2_15") (pintype "tri_state"))
    )
    (net (code "48") (name "Net-(U1A-D3)") (class "Default")
      (node (ref "R5") (pin "2") (pinfunction "2_2") (pintype "passive"))
      (node (ref "U1") (pin "8") (pinfunction "D3_8") (pintype "tri_state"))
    )
    (net (code "49") (name "Net-(U1A-D4)") (class "Default")
      (node (ref "R4") (pin "2") (pinfunction "2_2") (pintype "passive"))
      (node (ref "U1") (pin "18") (pinfunction "D4_18") (pintype "tri_state"))
    )
    (net (code "50") (name "Net-(U1A-D5)") (class "Default")
      (node (ref "R3") (pin "2") (pinfunction "2_2") (pintype "passive"))
      (node (ref "U1") (pin "19") (pinfunction "D5_19") (pintype "tri_state"))
    )
    (net (code "51") (name "Net-(U1A-D6)") (class "Default")
      (node (ref "R2") (pin "2") (pinfunction "2_2") (pintype "passive"))
      (node (ref "U1") (pin "20") (pinfunction "D6_20") (pintype "tri_state"))
    )
    (net (code "52") (name "Net-(U1A-D7)") (class "Default")
      (node (ref "R1") (pin "2") (pinfunction "2_2") (pintype "passive"))
      (node (ref "U1") (pin "21") (pinfunction "D7_21") (pintype "tri_state"))
    )
    (net (code "53") (name "Net-(U1A-EOC)") (class "Default")
      (node (ref "U1") (pin "6") (pinfunction "START_6") (pintype "input"))
      (node (ref "U1") (pin "7") (pinfunction "EOC_7") (pintype "output"))
    )
    (net (code "54") (name "Net-(U2A-A)") (class "Default")
      (node (ref "R24") (pin "1") (pinfunction "1_1") (pintype "passive"))
      (node (ref "R50") (pin "2") (pinfunction "2_2") (pintype "passive"))
      (node (ref "U2") (pin "11") (pinfunction "A_11") (pintype "input"))
      (node (ref "U6") (pin "13") (pinfunction "L7_13") (pintype "output"))
    )
    (net (code "55") (name "Net-(U2A-B)") (class "Default")
      (node (ref "R25") (pin "1") (pinfunction "1_1") (pintype "passive"))
      (node (ref "R49") (pin "2") (pinfunction "2_2") (pintype "passive"))
      (node (ref "U2") (pin "10") (pinfunction "B_10") (pintype "input"))
      (node (ref "U6") (pin "14") (pinfunction "L6_14") (pintype "output"))
    )
    (net (code "56") (name "Net-(U2A-C)") (class "Default")
      (node (ref "R26") (pin "1") (pinfunction "1_1") (pintype "passive"))
      (node (ref "R48") (pin "2") (pinfunction "2_2") (pintype "passive"))
      (node (ref "U2") (pin "9") (pinfunction "C_9") (pintype "input"))
      (node (ref "U6") (pin "15") (pinfunction "L5_15") (pintype "output"))
    )
    (net (code "57") (name "Net-(U2A-X)") (class "Default")
      (node (ref "R15") (pin "1") (pinfunction "1_1") (pintype "passive"))
      (node (ref "R16") (pin "1") (pinfunction "1_1") (pintype "passive"))
      (node (ref "U2") (pin "14") (pinfunction "X_14") (pintype "bidirectional"))
    )
    (net (code "58") (name "Net-(U2A-X0)") (class "Default")
      (node (ref "R8") (pin "1") (pinfunction "1_1") (pintype "passive"))
      (node (ref "U2") (pin "12") (pinfunction "X0_12") (pintype "bidirectional"))
    )
    (net (code "59") (name "Net-(U2A-X1)") (class "Default")
      (node (ref "R14") (pin "1") (pinfunction "1_1") (pintype "passive"))
      (node (ref "R15") (pin "2") (pinfunction "2_2") (pintype "passive"))
      (node (ref "U2") (pin "13") (pinfunction "X1_13") (pintype "bidirectional"))
      (node (ref "U2") (pin "15") (pinfunction "Y_15") (pintype "bidirectional"))
    )
    (net (code "60") (name "Net-(U2A-Y0)") (class "Default")
      (node (ref "R7") (pin "1") (pinfunction "1_1") (pintype "passive"))
      (node (ref "U2") (pin "2") (pinfunction "Y0_2") (pintype "bidirectional"))
    )
    (net (code "61") (name "Net-(U2A-Y1)") (class "Default")
      (node (ref "R13") (pin "1") (pinfunction "1_1") (pintype "passive"))
      (node (ref "R14") (pin "2") (pinfunction "2_2") (pintype "passive"))
      (node (ref "U2") (pin "1") (pinfunction "Y1_1") (pintype "bidirectional"))
      (node (ref "U2") (pin "4") (pinfunction "Z_4") (pintype "bidirectional"))
    )
    (net (code "62") (name "Net-(U2A-Z0)") (class "Default")
      (node (ref "R6") (pin "1") (pinfunction "1_1") (pintype "passive"))
      (node (ref "U2") (pin "5") (pinfunction "Z0_5") (pintype "bidirectional"))
    )
    (net (code "63") (name "Net-(U2A-Z1)") (class "Default")
      (node (ref "R12") (pin "1") (pinfunction "1_1") (pintype "passive"))
      (node (ref "R13") (pin "2") (pinfunction "2_2") (pintype "passive"))
      (node (ref "U2") (pin "3") (pinfunction "Z1_3") (pintype "bidirectional"))
      (node (ref "U3") (pin "14") (pinfunction "X_14") (pintype "bidirectional"))
    )
    (net (code "64") (name "Net-(U3A-A)") (class "Default")
      (node (ref "R27") (pin "1") (pinfunction "1_1") (pintype "passive"))
      (node (ref "R47") (pin "2") (pinfunction "2_2") (pintype "passive"))
      (node (ref "U3") (pin "11") (pinfunction "A_11") (pintype "input"))
      (node (ref "U6") (pin "16") (pinfunction "L4_16") (pintype "output"))
    )
    (net (code "65") (name "Net-(U3A-B)") (class "Default")
      (node (ref "R28") (pin "1") (pinfunction "1_1") (pintype "passive"))
      (node (ref "R46") (pin "2") (pinfunction "2_2") (pintype "passive"))
      (node (ref "U3") (pin "10") (pinfunction "B_10") (pintype "input"))
      (node (ref "U6") (pin "17") (pinfunction "L3_17") (pintype "output"))
    )
    (net (code "66") (name "Net-(U3A-C)") (class "Default")
      (node (ref "R29") (pin "1") (pinfunction "1_1") (pintype "passive"))
      (node (ref "R45") (pin "2") (pinfunction "2_2") (pintype "passive"))
      (node (ref "U3") (pin "9") (pinfunction "C_9") (pintype "input"))
      (node (ref "U6") (pin "18") (pinfunction "L2_18") (pintype "output"))
    )
    (net (code "67") (name "Net-(U3A-X0)") (class "Default")
      (node (ref "R5") (pin "1") (pinfunction "1_1") (pintype "passive"))
      (node (ref "U3") (pin "12") (pinfunction "X0_12") (pintype "bidirectional"))
    )
    (net (code "68") (name "Net-(U3A-X1)") (class "Default")
      (node (ref "R11") (pin "1") (pinfunction "1_1") (pintype "passive"))
      (node (ref "R12") (pin "2") (pinfunction "2_2") (pintype "passive"))
      (node (ref "U3") (pin "13") (pinfunction "X1_13") (pintype "bidirectional"))
      (node (ref "U3") (pin "15") (pinfunction "Y_15") (pintype "bidirectional"))
    )
    (net (code "69") (name "Net-(U3A-Y0)") (class "Default")
      (node (ref "R4") (pin "1") (pinfunction "1_1") (pintype "passive"))
      (node (ref "U3") (pin "2") (pinfunction "Y0_2") (pintype "bidirectional"))
    )
    (net (code "70") (name "Net-(U3A-Y1)") (class "Default")
      (node (ref "R10") (pin "1") (pinfunction "1_1") (pintype "passive"))
      (node (ref "R11") (pin "2") (pinfunction "2_2") (pintype "passive"))
      (node (ref "U3") (pin "1") (pinfunction "Y1_1") (pintype "bidirectional"))
      (node (ref "U3") (pin "4") (pinfunction "Z_4") (pintype "bidirectional"))
    )
    (net (code "71") (name "Net-(U3A-Z0)") (class "Default")
      (node (ref "R3") (pin "1") (pinfunction "1_1") (pintype "passive"))
      (node (ref "U3") (pin "5") (pinfunction "Z0_5") (pintype "bidirectional"))
    )
    (net (code "72") (name "Net-(U3A-Z1)") (class "Default")
      (node (ref "R10") (pin "2") (pinfunction "2_2") (pintype "passive"))
      (node (ref "R9") (pin "1") (pinfunction "1_1") (pintype "passive"))
      (node (ref "U3") (pin "3") (pinfunction "Z1_3") (pintype "bidirectional"))
      (node (ref "U4") (pin "4") (pinfunction "X_4") (pintype "bidirectional"))
    )
    (net (code "73") (name "Net-(U4A-A)") (class "Default")
      (node (ref "R2") (pin "1") (pinfunction "1_1") (pintype "passive"))
      (node (ref "U4") (pin "3") (pinfunction "A_3") (pintype "bidirectional"))
    )
    (net (code "74") (name "Net-(U4A-B)") (class "Default")
      (node (ref "R1") (pin "1") (pinfunction "1_1") (pintype "passive"))
      (node (ref "R9") (pin "2") (pinfunction "2_2") (pintype "passive"))
      (node (ref "U4") (pin "1") (pinfunction "B_1") (pintype "bidirectional"))
      (node (ref "U5") (pin "5") (pinfunction "+IN_5") (pintype "input"))
    )
    (net (code "75") (name "Net-(U4A-~{A}{slash}B)") (class "Default")
      (node (ref "R30") (pin "1") (pinfunction "1_1") (pintype "passive"))
      (node (ref "R44") (pin "2") (pinfunction "2_2") (pintype "passive"))
      (node (ref "U4") (pin "6") (pinfunction "~{A}/B_6") (pintype "input"))
      (node (ref "U6") (pin "1") (pinfunction "L1_1") (pintype "output"))
    )
    (net (code "76") (name "Net-(U5A-+IN)") (class "Default")
      (node (ref "R32") (pin "2") (pinfunction "2_2") (pintype "passive"))
      (node (ref "R33") (pin "2") (pinfunction "2_2") (pintype "passive"))
      (node (ref "U5") (pin "3") (pinfunction "+IN_3") (pintype "input"))
    )
    (net (code "77") (name "Net-(U5A--IN)") (class "Default")
      (node (ref "R20") (pin "2") (pinfunction "2_2") (pintype "bidirectional"))
      (node (ref "R20") (pin "3") (pinfunction "3_3") (pintype "bidirectional"))
      (node (ref "R36") (pin "1") (pinfunction "1_1") (pintype "passive"))
      (node (ref "U5") (pin "2") (pinfunction "-IN_2") (pintype "input"))
    )
    (net (code "78") (name "Net-(U5A-OUT)") (class "Default")
      (node (ref "R18") (pin "1") (pinfunction "1_1") (pintype "passive"))
      (node (ref "R35") (pin "2") (pinfunction "2_2") (pintype "passive"))
      (node (ref "U5") (pin "1") (pinfunction "OUT_1") (pintype "output"))
    )
    (net (code "79") (name "Net-(U5B--IN)") (class "Default")
      (node (ref "R31") (pin "2") (pinfunction "2_2") (pintype "passive"))
      (node (ref "R51") (pin "1") (pinfunction "1_1") (pintype "passive"))
      (node (ref "U5") (pin "6") (pinfunction "-IN_6") (pintype "input"))
    )
    (net (code "80") (name "Net-(U5B-OUT)") (class "Default")
      (node (ref "R31") (pin "1") (pinfunction "1_1") (pintype "passive"))
      (node (ref "R38") (pin "2") (pinfunction "2_2") (pintype "passive"))
      (node (ref "U5") (pin "7") (pinfunction "OUT_7") (pintype "output"))
    )
    (net (code "81") (name "Net-(U6-SIG)") (class "Default")
      (node (ref "C17") (pin "2") (pinfunction "2_2") (pintype "passive"))
      (node (ref "R61") (pin "1") (pinfunction "1_1") (pintype "passive"))
      (node (ref "U6") (pin "5") (pinfunction "SIG_5") (pintype "input"))
    )
    (net (code "82") (name "Net-(U6-VR)") (class "Default")
      (node (ref "R54") (pin "2") (pinfunction "2_2") (pintype "passive"))
      (node (ref "U6") (pin "7") (pinfunction "VR_7") (pintype "output"))
    )
    (net (code "83") (name "Net-(U7-CV)") (class "Default")
      (node (ref "C5") (pin "2") (pinfunction "2_2") (pintype "passive"))
      (node (ref "U7") (pin "5") (pinfunction "CV_5") (pintype "input"))
    )
    (net (code "84") (name "unconnected-(U6-L8-Pad12)") (class "Default")
      (node (ref "U6") (pin "12") (pinfunction "L8_12") (pintype "output"))
    )
    (net (code "85") (name "unconnected-(U6-L9-Pad11)") (class "Default")
      (node (ref "U6") (pin "11") (pinfunction "L9_11") (pintype "output"))
    )
    (net (code "86") (name "unconnected-(U6-L10-Pad10)") (class "Default")
      (node (ref "U6") (pin "10") (pinfunction "L10_10") (pintype "output"))
    )
  )
)
